# gpio.net
KiCad netlist of a schematic drawn in Altium Designer
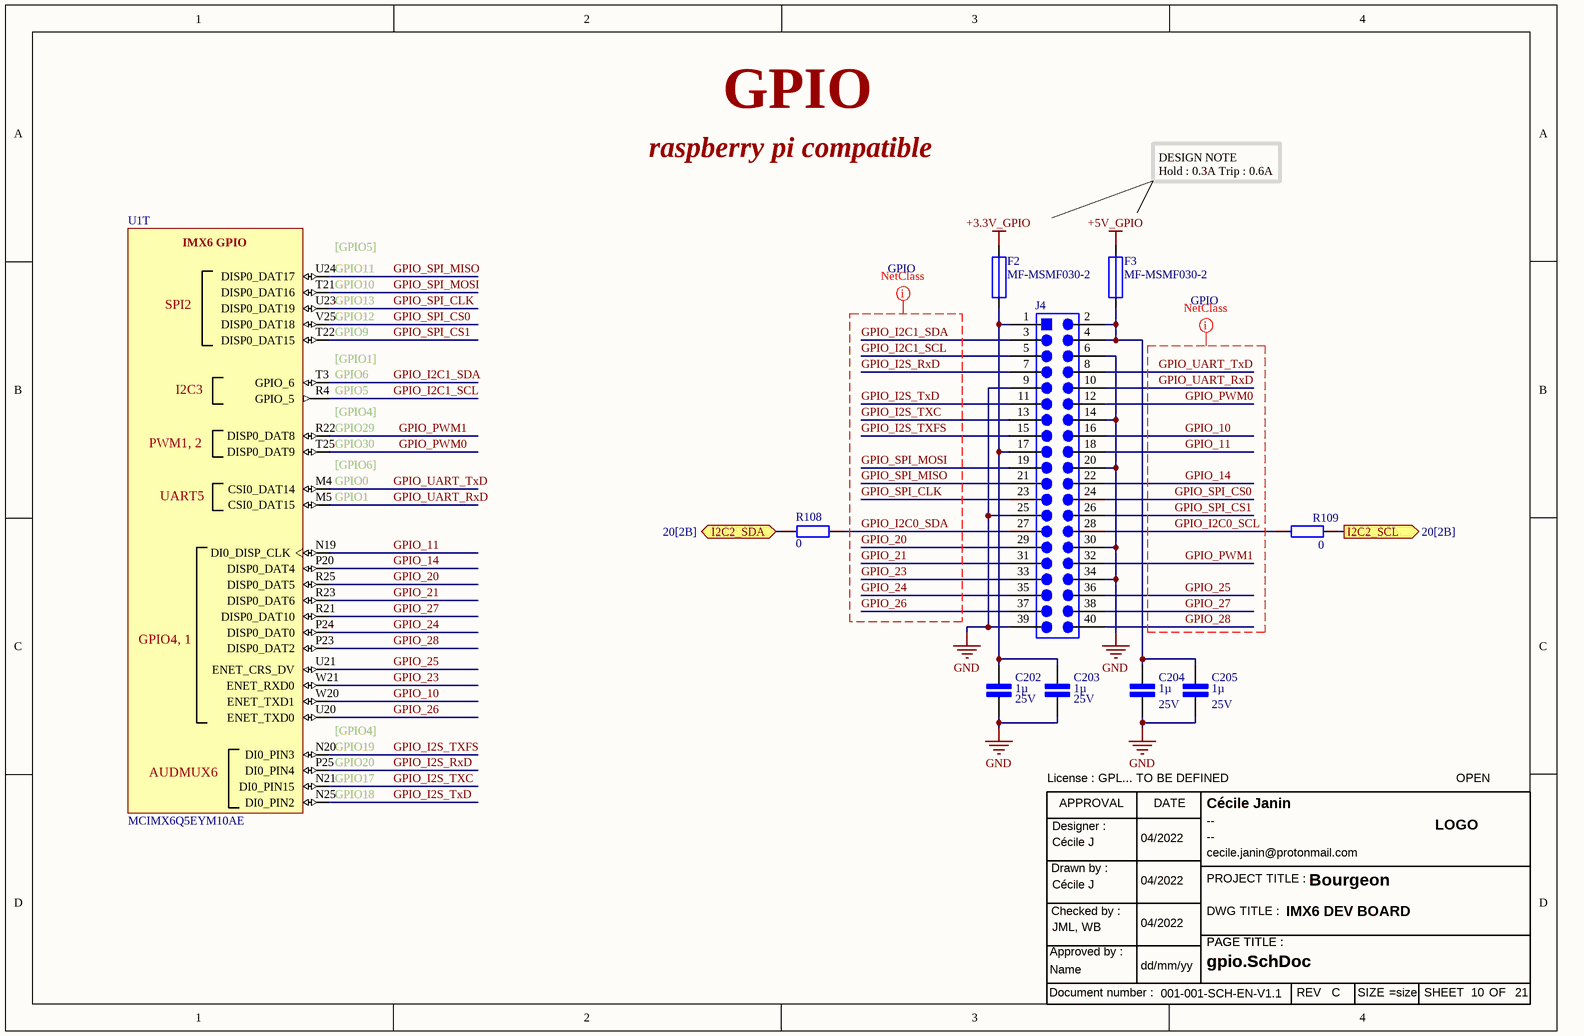
[diagram p0: gpio.SchDoc]

(export (version "E")
  (design (tool "Eeschema 10.0.6"))
  (components
    (comp (ref "C202")
      (value "1µ")
      (footprint "Cap cer 0402/1005")
      (description "cap cer 1µ 25V 10% X5R 0402")
      (fields (field (name "TENSION DU DIÉLECTRIQUE") "25V"))
      (libsource (lib "First Board IMX6") (part "cap 1µ 25V"))
    )
    (comp (ref "C203")
      (value "1µ")
      (footprint "Cap cer 0402/1005")
      (description "cap cer 1µ 25V 10% X5R 0402")
      (fields (field (name "TENSION DU DIÉLECTRIQUE") "25V"))
      (libsource (lib "First Board IMX6") (part "cap 1µ 25V"))
    )
    (comp (ref "C204")
      (value "1µ")
      (footprint "Cap cer 0402/1005")
      (description "cap cer 1µ 25V 10% X5R 0402")
      (fields (field (name "TENSION DU DIÉLECTRIQUE") "25V"))
      (libsource (lib "") (part "cap 1µ 25V_1"))
    )
    (comp (ref "C205")
      (value "1µ")
      (footprint "Cap cer 0402/1005")
      (description "cap cer 1µ 25V 10% X5R 0402")
      (fields (field (name "TENSION DU DIÉLECTRIQUE") "25V"))
      (libsource (lib "") (part "cap 1µ 25V_1"))
    )
    (comp (ref "F2")
      (value "MF-MSMF030-2")
      (footprint "Fuse 1812/4532 MF-MSMF050-2")
      (description "Hold : 0.3A, trip 0.6A 30V 1812")
      (libsource (lib "First Board IMX6") (part "Fuse PPTC 0.3A"))
    )
    (comp (ref "F3")
      (value "MF-MSMF030-2")
      (footprint "Fuse 1812/4532 MF-MSMF050-2")
      (description "Hold : 0.3A, trip 0.6A 30V 1812")
      (libsource (lib "First Board IMX6") (part "Fuse PPTC 0.3A"))
    )
    (comp (ref "J4")
      (value "header_rasppi_61304021121")
      (footprint "header_rasppi_61304021121")
      (description "header raspberry pi compatible")
      (libsource (lib "First Board IMX6") (part "header_rasppi_61304021121"))
    )
    (comp (ref "R108")
      (value "0")
      (footprint "Res 0603/1603")
      (description "res 0603")
      (libsource (lib "First Board IMX6") (part "res 0Ohm"))
    )
    (comp (ref "R109")
      (value "0")
      (footprint "Res 0603/1603")
      (description "res 0603")
      (libsource (lib "First Board IMX6") (part "res 0Ohm"))
    )
    (comp (ref "TB9")
      (value "Title bloc ANSI modified")
      (libsource (lib "First Board IMX6") (part "Title bloc ANSI"))
    )
    (comp (ref "U1")
      (value "MCIMX6Q5EYM10AE")
      (footprint "FRES-2197-01")
      (fields
        (field (name "PARTNUMBER") "MCIMX6Q5EYM10ACR")
        (field (name "MANUFACTURER") "Freescale Semiconductor")
      )
      (libsource (lib "First Board IMX6") (part "IMX6Q5EYM10AE"))
    )
  )
  (nets
    (net (code "1") (name "+3.3V_GPIO") (class "Default")
      (node (ref "F2") (pin "2") (pinfunction "2_2") (pintype "passive"))
    )
    (net (code "2") (name "+5V_GPIO") (class "Default")
      (node (ref "F3") (pin "2") (pinfunction "2_2") (pintype "passive"))
    )
    (net (code "3") (name "/GPIO_10") (class "Default")
      (node (ref "J4") (pin "16") (pinfunction "16_16") (pintype "passive"))
      (node (ref "U1") (pin "W20") (pinfunction "ENET_TXD1_W20") (pintype "bidirectional"))
    )
    (net (code "4") (name "/GPIO_11") (class "Default")
      (node (ref "J4") (pin "18") (pinfunction "18_18") (pintype "passive"))
      (node (ref "U1") (pin "N19") (pinfunction "DI0_DISP_CLK_N19") (pintype "bidirectional"))
    )
    (net (code "5") (name "/GPIO_14") (class "Default")
      (node (ref "J4") (pin "22") (pinfunction "22_22") (pintype "passive"))
      (node (ref "U1") (pin "P20") (pinfunction "DISP0_DAT4_P20") (pintype "bidirectional"))
    )
    (net (code "6") (name "/GPIO_20") (class "Default")
      (node (ref "J4") (pin "29") (pinfunction "29_29") (pintype "passive"))
      (node (ref "U1") (pin "R25") (pinfunction "DISP0_DAT5_R25") (pintype "bidirectional"))
    )
    (net (code "7") (name "/GPIO_21") (class "Default")
      (node (ref "J4") (pin "31") (pinfunction "31_31") (pintype "passive"))
      (node (ref "U1") (pin "R23") (pinfunction "DISP0_DAT6_R23") (pintype "bidirectional"))
    )
    (net (code "8") (name "/GPIO_23") (class "Default")
      (node (ref "J4") (pin "33") (pinfunction "33_33") (pintype "passive"))
      (node (ref "U1") (pin "W21") (pinfunction "ENET_RXD0_W21") (pintype "bidirectional"))
    )
    (net (code "9") (name "/GPIO_24") (class "Default")
      (node (ref "J4") (pin "35") (pinfunction "35_35") (pintype "passive"))
      (node (ref "U1") (pin "P24") (pinfunction "DISP0_DAT0_P24") (pintype "bidirectional"))
    )
    (net (code "10") (name "/GPIO_25") (class "Default")
      (node (ref "J4") (pin "36") (pinfunction "36_36") (pintype "passive"))
      (node (ref "U1") (pin "U21") (pinfunction "ENET_CRS_DV_U21") (pintype "bidirectional"))
    )
    (net (code "11") (name "/GPIO_26") (class "Default")
      (node (ref "J4") (pin "37") (pinfunction "37_37") (pintype "passive"))
      (node (ref "U1") (pin "U20") (pinfunction "ENET_TXD0_U20") (pintype "bidirectional"))
    )
    (net (code "12") (name "/GPIO_27") (class "Default")
      (node (ref "J4") (pin "38") (pinfunction "38_38") (pintype "passive"))
      (node (ref "U1") (pin "R21") (pinfunction "DISP0_DAT10_R21") (pintype "bidirectional"))
    )
    (net (code "13") (name "/GPIO_28") (class "Default")
      (node (ref "J4") (pin "40") (pinfunction "40_40") (pintype "passive"))
      (node (ref "U1") (pin "P23") (pinfunction "DISP0_DAT2_P23") (pintype "bidirectional"))
    )
    (net (code "14") (name "/GPIO_I2C0_SCL") (class "Default")
      (node (ref "J4") (pin "28") (pinfunction "28_28") (pintype "passive"))
      (node (ref "R109") (pin "1") (pintype "passive"))
    )
    (net (code "15") (name "/GPIO_I2C0_SDA") (class "Default")
      (node (ref "J4") (pin "27") (pinfunction "27_27") (pintype "passive"))
      (node (ref "R108") (pin "2") (pintype "passive"))
    )
    (net (code "16") (name "/GPIO_I2C1_SCL") (class "Default")
      (node (ref "J4") (pin "5") (pinfunction "5_5") (pintype "passive"))
      (node (ref "U1") (pin "R4") (pinfunction "GPIO_5_R4") (pintype "output"))
    )
    (net (code "17") (name "/GPIO_I2C1_SDA") (class "Default")
      (node (ref "J4") (pin "3") (pinfunction "3_3") (pintype "passive"))
      (node (ref "U1") (pin "T3") (pinfunction "GPIO_6_T3") (pintype "bidirectional"))
    )
    (net (code "18") (name "/GPIO_I2S_RxD") (class "Default")
      (node (ref "J4") (pin "7") (pinfunction "7_7") (pintype "passive"))
      (node (ref "U1") (pin "P25") (pinfunction "DI0_PIN4_P25") (pintype "bidirectional"))
    )
    (net (code "19") (name "/GPIO_I2S_TXC") (class "Default")
      (node (ref "J4") (pin "13") (pinfunction "13_13") (pintype "passive"))
      (node (ref "U1") (pin "N21") (pinfunction "DI0_PIN15_N21") (pintype "bidirectional"))
    )
    (net (code "20") (name "/GPIO_I2S_TXFS") (class "Default")
      (node (ref "J4") (pin "15") (pinfunction "15_15") (pintype "passive"))
      (node (ref "U1") (pin "N20") (pinfunction "DI0_PIN3_N20") (pintype "bidirectional"))
    )
    (net (code "21") (name "/GPIO_I2S_TxD") (class "Default")
      (node (ref "J4") (pin "11") (pinfunction "11_11") (pintype "passive"))
      (node (ref "U1") (pin "N25") (pinfunction "DI0_PIN2_N25") (pintype "bidirectional"))
    )
    (net (code "22") (name "/GPIO_PWM0") (class "Default")
      (node (ref "J4") (pin "12") (pinfunction "12_12") (pintype "passive"))
      (node (ref "U1") (pin "T25") (pinfunction "DISP0_DAT9_T25") (pintype "bidirectional"))
    )
    (net (code "23") (name "/GPIO_PWM1") (class "Default")
      (node (ref "J4") (pin "32") (pinfunction "32_32") (pintype "passive"))
      (node (ref "U1") (pin "R22") (pinfunction "DISP0_DAT8_R22") (pintype "bidirectional"))
    )
    (net (code "24") (name "/GPIO_SPI_CLK") (class "Default")
      (node (ref "J4") (pin "23") (pinfunction "23_23") (pintype "passive"))
      (node (ref "U1") (pin "U23") (pinfunction "DISP0_DAT19_U23") (pintype "bidirectional"))
    )
    (net (code "25") (name "/GPIO_SPI_CS0") (class "Default")
      (node (ref "J4") (pin "24") (pinfunction "24_24") (pintype "passive"))
      (node (ref "U1") (pin "V25") (pinfunction "DISP0_DAT18_V25") (pintype "bidirectional"))
    )
    (net (code "26") (name "/GPIO_SPI_CS1") (class "Default")
      (node (ref "J4") (pin "26") (pinfunction "26_26") (pintype "passive"))
      (node (ref "U1") (pin "T22") (pinfunction "DISP0_DAT15_T22") (pintype "bidirectional"))
    )
    (net (code "27") (name "/GPIO_SPI_MISO") (class "Default")
      (node (ref "J4") (pin "21") (pinfunction "21_21") (pintype "passive"))
      (node (ref "U1") (pin "U24") (pinfunction "DISP0_DAT17_U24") (pintype "bidirectional"))
    )
    (net (code "28") (name "/GPIO_SPI_MOSI") (class "Default")
      (node (ref "J4") (pin "19") (pinfunction "19_19") (pintype "passive"))
      (node (ref "U1") (pin "T21") (pinfunction "DISP0_DAT16_T21") (pintype "bidirectional"))
    )
    (net (code "29") (name "/GPIO_UART_RxD") (class "Default")
      (node (ref "J4") (pin "10") (pinfunction "10_10") (pintype "passive"))
      (node (ref "U1") (pin "M5") (pinfunction "CSI0_DAT15_M5") (pintype "bidirectional"))
    )
    (net (code "30") (name "/GPIO_UART_TxD") (class "Default")
      (node (ref "J4") (pin "8") (pinfunction "8_8") (pintype "passive"))
      (node (ref "U1") (pin "M4") (pinfunction "CSI0_DAT14_M4") (pintype "bidirectional"))
    )
    (net (code "31") (name "/I2C2_SCL") (class "Default") (node (ref "R109") (pin "2") (pintype "passive")))
    (net (code "32") (name "/I2C2_SDA") (class "Default") (node (ref "R108") (pin "1") (pintype "passive")))
    (net (code "33") (name "GND") (class "Default")
      (node (ref "C202") (pin "2") (pinfunction "4_2") (pintype "passive"))
      (node (ref "C203") (pin "2") (pinfunction "4_2") (pintype "passive"))
      (node (ref "C204") (pin "2") (pinfunction "4_2") (pintype "passive"))
      (node (ref "C205") (pin "2") (pinfunction "4_2") (pintype "passive"))
      (node (ref "J4") (pin "14") (pinfunction "14_14") (pintype "passive"))
      (node (ref "J4") (pin "20") (pinfunction "20_20") (pintype "passive"))
      (node (ref "J4") (pin "25") (pinfunction "25_25") (pintype "passive"))
      (node (ref "J4") (pin "30") (pinfunction "30_30") (pintype "passive"))
      (node (ref "J4") (pin "34") (pinfunction "34_34") (pintype "passive"))
      (node (ref "J4") (pin "39") (pinfunction "39_39") (pintype "passive"))
      (node (ref "J4") (pin "6") (pinfunction "6_6") (pintype "passive"))
      (node (ref "J4") (pin "9") (pinfunction "9_9") (pintype "passive"))
    )
    (net (code "34") (name "Net-(C202-3)") (class "Default")
      (node (ref "C202") (pin "1") (pinfunction "3_1") (pintype "passive"))
      (node (ref "C203") (pin "1") (pinfunction "3_1") (pintype "passive"))
      (node (ref "F2") (pin "1") (pinfunction "1_1") (pintype "passive"))
      (node (ref "J4") (pin "1") (pinfunction "1_1") (pintype "passive"))
      (node (ref "J4") (pin "17") (pinfunction "17_17") (pintype "passive"))
    )
    (net (code "35") (name "Net-(C204-3)") (class "Default")
      (node (ref "C204") (pin "1") (pinfunction "3_1") (pintype "passive"))
      (node (ref "C205") (pin "1") (pinfunction "3_1") (pintype "passive"))
      (node (ref "F3") (pin "1") (pinfunction "1_1") (pintype "passive"))
      (node (ref "J4") (pin "2") (pinfunction "2_2") (pintype "passive"))
      (node (ref "J4") (pin "4") (pinfunction "4_4") (pintype "passive"))
    )
  )
)
